# MES.net
KiCad netlist of a schematic drawn in Altium Designer
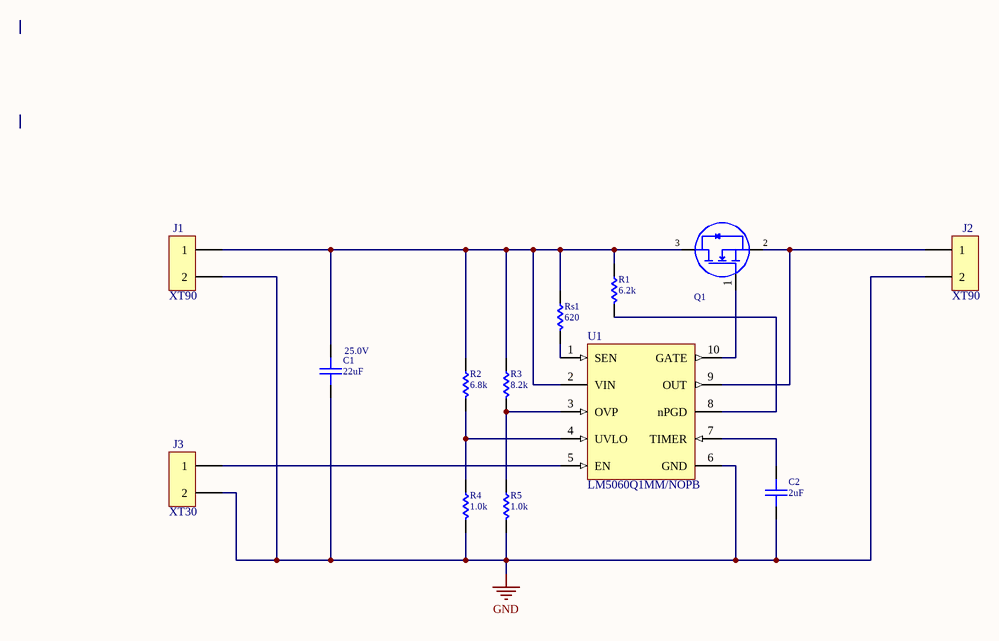
[diagram p0: MES.SchDoc]

(export (version "E")
  (design (tool "Eeschema 10.0.6"))
  (components
    (comp (ref "C1")
      (value "Ceramic Capacitor")
      (footprint "Component 0805")
      (fields (field (name "CAPACITANCE") "22uF") (field (name "VOLTAGE") "25.0V"))
      (libsource (lib "MechatronicsSCH") (part "Capacitor, Ceramic"))
    )
    (comp (ref "C2")
      (value "Ceramic Capacitor")
      (footprint "Component 0805")
      (fields (field (name "CAPACITANCE") "2uF"))
      (libsource (lib "MechatronicsSCH") (part "Capacitor, Ceramic"))
    )
    (comp (ref "J1")
      (value "Connector, XT90")
      (fields (field (name "TYPE") "XT90"))
      (libsource (lib "") (part "Connector, XT90_1"))
    )
    (comp (ref "J2")
      (value "Connector, XT90")
      (fields (field (name "TYPE") "XT90"))
      (libsource (lib "MechatronicsSCH") (part "Connector, XT90"))
    )
    (comp (ref "J3")
      (value "Connector, XT90")
      (fields (field (name "TYPE") "XT30"))
      (libsource (lib "") (part "Connector, XT90_1"))
    )
    (comp (ref "Q1")
      (value "IXFN360N10T")
      (footprint "IXFN360N10T")
      (description "N-Channel MOSFET 830W")
      (libsource (lib "MechatronicsSCH") (part "IXFN360N10T"))
    )
    (comp (ref "R1")
      (value "Resistor")
      (footprint "Component 0805")
      (description "Thick Film Resistors - SMD 1/16watt 1%")
      (fields (field (name "RESISTANCE") "6.2k"))
      (libsource (lib "MechatronicsSCH") (part "Resistor"))
    )
    (comp (ref "R2")
      (value "Resistor")
      (footprint "Component 0805")
      (description "Thick Film Resistors - SMD 1/16watt 1%")
      (fields (field (name "RESISTANCE") "6.8k"))
      (libsource (lib "MechatronicsSCH") (part "Resistor"))
    )
    (comp (ref "R3")
      (value "Resistor")
      (footprint "Component 0805")
      (description "Thick Film Resistors - SMD 1/16watt 1%")
      (fields (field (name "RESISTANCE") "8.2k"))
      (libsource (lib "MechatronicsSCH") (part "Resistor"))
    )
    (comp (ref "R4")
      (value "Resistor")
      (footprint "Component 0805")
      (description "Thick Film Resistors - SMD 1/16watt 1%")
      (fields (field (name "RESISTANCE") "1.0k"))
      (libsource (lib "MechatronicsSCH") (part "Resistor"))
    )
    (comp (ref "R5")
      (value "Resistor")
      (footprint "Component 0805")
      (description "Thick Film Resistors - SMD 1/16watt 1%")
      (fields (field (name "RESISTANCE") "1.0k"))
      (libsource (lib "MechatronicsSCH") (part "Resistor"))
    )
    (comp (ref "Rs1")
      (value "Resistor")
      (footprint "Component 0805")
      (description "Thick Film Resistors - SMD 1/16watt 1%")
      (fields (field (name "RESISTANCE") "620"))
      (libsource (lib "MechatronicsSCH") (part "Resistor"))
    )
    (comp (ref "U1")
      (value "LM5060Q1MM/NOPB")
      (footprint "MUB10A_N")
      (description "High-Side Protection Controller with Low Quiescent Current, 10-pin MSOP, Pb-Free")
      (fields (field (name "MANUFACTURER") "National Semiconductor"))
      (libsource (lib "Texas_Instruments_LM5060Q1MM_NOPB") (part "LM5060Q1MM/NOPB"))
    )
  )
  (nets
    (net (code "1") (name "GND") (class "Default")
      (node (ref "C1") (pin "2") (pinfunction "2_2") (pintype "passive"))
      (node (ref "C2") (pin "2") (pinfunction "2_2") (pintype "passive"))
      (node (ref "J1") (pin "2") (pinfunction "2_2") (pintype "passive"))
      (node (ref "J2") (pin "2") (pinfunction "2_2") (pintype "passive"))
      (node (ref "J3") (pin "2") (pinfunction "2_2") (pintype "passive"))
      (node (ref "R4") (pin "2") (pinfunction "2_2") (pintype "passive"))
      (node (ref "R5") (pin "2") (pinfunction "2_2") (pintype "passive"))
      (node (ref "U1") (pin "6") (pinfunction "GND_6") (pintype "power_in"))
    )
    (net (code "2") (name "Net-(Q1-Drain)") (class "Default")
      (node (ref "C1") (pin "1") (pinfunction "1_1") (pintype "passive"))
      (node (ref "J1") (pin "1") (pinfunction "1_1") (pintype "passive"))
      (node (ref "Q1") (pin "3") (pinfunction "Drain_3") (pintype "passive"))
      (node (ref "R1") (pin "1") (pinfunction "1_1") (pintype "passive"))
      (node (ref "R2") (pin "1") (pinfunction "1_1") (pintype "passive"))
      (node (ref "R3") (pin "1") (pinfunction "1_1") (pintype "passive"))
      (node (ref "Rs1") (pin "1") (pinfunction "1_1") (pintype "passive"))
      (node (ref "U1") (pin "2") (pinfunction "VIN_2") (pintype "power_in"))
    )
    (net (code "3") (name "Net-(Q1-Gate)") (class "Default")
      (node (ref "Q1") (pin "1") (pinfunction "Gate_1") (pintype "passive"))
      (node (ref "U1") (pin "10") (pinfunction "GATE_10") (pintype "output"))
    )
    (net (code "4") (name "Net-(Q1-Source)") (class "Default")
      (node (ref "J2") (pin "1") (pinfunction "1_1") (pintype "passive"))
      (node (ref "Q1") (pin "2") (pinfunction "Source_2") (pintype "passive"))
      (node (ref "U1") (pin "9") (pinfunction "OUT_9") (pintype "output"))
    )
    (net (code "5") (name "Net-(U1-EN)") (class "Default")
      (node (ref "J3") (pin "1") (pinfunction "1_1") (pintype "passive"))
      (node (ref "U1") (pin "5") (pinfunction "EN_5") (pintype "input"))
    )
    (net (code "6") (name "Net-(U1-OVP)") (class "Default")
      (node (ref "R3") (pin "2") (pinfunction "2_2") (pintype "passive"))
      (node (ref "R5") (pin "1") (pinfunction "1_1") (pintype "passive"))
      (node (ref "U1") (pin "3") (pinfunction "OVP_3") (pintype "input"))
    )
    (net (code "7") (name "Net-(U1-SEN)") (class "Default")
      (node (ref "Rs1") (pin "2") (pinfunction "2_2") (pintype "passive"))
      (node (ref "U1") (pin "1") (pinfunction "SEN_1") (pintype "input"))
    )
    (net (code "8") (name "Net-(U1-TIMER)") (class "Default")
      (node (ref "C2") (pin "1") (pinfunction "1_1") (pintype "passive"))
      (node (ref "U1") (pin "7") (pinfunction "TIMER_7") (pintype "input"))
    )
    (net (code "9") (name "Net-(U1-UVLO)") (class "Default")
      (node (ref "R2") (pin "2") (pinfunction "2_2") (pintype "passive"))
      (node (ref "R4") (pin "1") (pinfunction "1_1") (pintype "passive"))
      (node (ref "U1") (pin "4") (pinfunction "UVLO_4") (pintype "input"))
    )
    (net (code "10") (name "Net-(U1-nPGD)") (class "Default")
      (node (ref "R1") (pin "2") (pinfunction "2_2") (pintype "passive"))
      (node (ref "U1") (pin "8") (pinfunction "nPGD_8") (pintype "open_collector"))
    )
  )
)
